# gleis-a-1.net
KiCad netlist of a schematic drawn in EAGLE
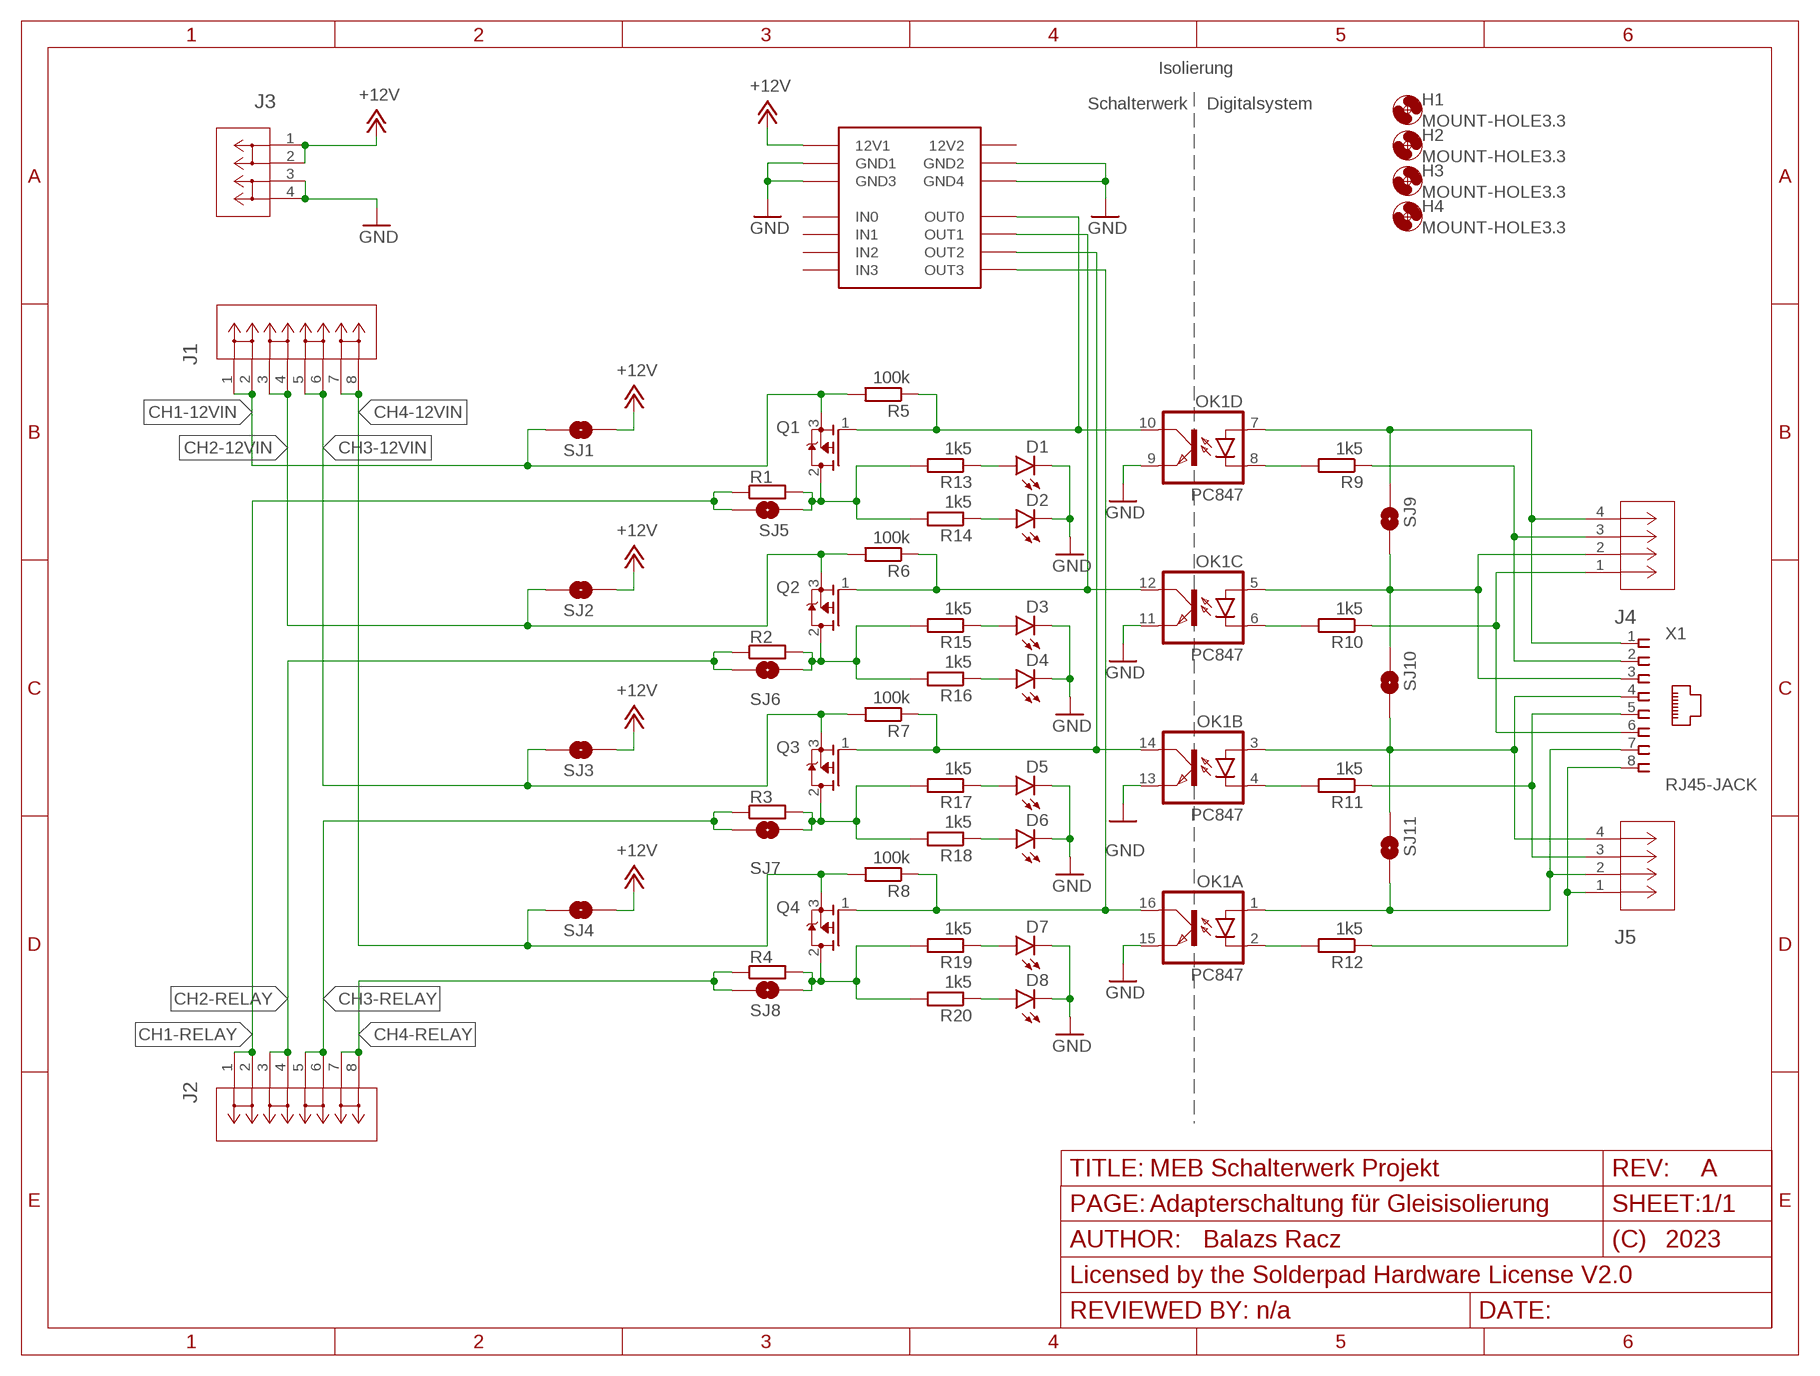
[diagram p0: schematic, sheet 1]

(export (version "E")
  (design (tool "Eeschema 10.0.6"))
  (components
    (comp (ref "D1")
      (value "LEDCHIPLED_0603")
      (footprint "eagle-import:CHIPLED_0603")
      (libsource (lib "eagle-import") (part "LEDCHIPLED_0603"))
    )
    (comp (ref "D2")
      (value "LEDHEADER")
      (footprint "eagle-import:LEDHEADER")
      (libsource (lib "eagle-import") (part "LEDHEADER"))
    )
    (comp (ref "D3")
      (value "LEDCHIPLED_0603")
      (footprint "eagle-import:CHIPLED_0603")
      (libsource (lib "eagle-import") (part "LEDCHIPLED_0603"))
    )
    (comp (ref "D4")
      (value "LEDHEADER")
      (footprint "eagle-import:LEDHEADER")
      (libsource (lib "eagle-import") (part "LEDHEADER"))
    )
    (comp (ref "D5")
      (value "LEDCHIPLED_0603")
      (footprint "eagle-import:CHIPLED_0603")
      (libsource (lib "eagle-import") (part "LEDCHIPLED_0603"))
    )
    (comp (ref "D6")
      (value "LEDHEADER")
      (footprint "eagle-import:LEDHEADER")
      (libsource (lib "eagle-import") (part "LEDHEADER"))
    )
    (comp (ref "D7")
      (value "LEDCHIPLED_0603")
      (footprint "eagle-import:CHIPLED_0603")
      (libsource (lib "eagle-import") (part "LEDCHIPLED_0603"))
    )
    (comp (ref "D8")
      (value "LEDHEADER")
      (footprint "eagle-import:LEDHEADER")
      (libsource (lib "eagle-import") (part "LEDHEADER"))
    )
    (comp (ref "H1")
      (value "MOUNT-HOLE3.3")
      (footprint "eagle-import:3,3")
      (libsource (lib "eagle-import") (part "MOUNT-HOLE3.3"))
    )
    (comp (ref "H2")
      (value "MOUNT-HOLE3.3")
      (footprint "eagle-import:3,3")
      (libsource (lib "eagle-import") (part "MOUNT-HOLE3.3"))
    )
    (comp (ref "H3")
      (value "MOUNT-HOLE3.3")
      (footprint "eagle-import:3,3")
      (libsource (lib "eagle-import") (part "MOUNT-HOLE3.3"))
    )
    (comp (ref "H4")
      (value "MOUNT-HOLE3.3")
      (footprint "eagle-import:3,3")
      (libsource (lib "eagle-import") (part "MOUNT-HOLE3.3"))
    )
    (comp (ref "J1")
      (value "PHNX_4P_508CONN_1017493")
      (footprint "eagle-import:PHNX_4P_508")
      (fields
        (field (name "MANUFACTURER_PART_NUMBER") "1017505")
        (field (name "COPYRIGHT") "Copyright (C) 2023 Ultra Librarian. All rights reserved.")
      )
      (libsource (lib "eagle-import") (part "PHNX_4P_508CONN_1017493"))
    )
    (comp (ref "J2")
      (value "PHNX_4P_508CONN_1017493")
      (footprint "eagle-import:PHNX_4P_508")
      (fields
        (field (name "MANUFACTURER_PART_NUMBER") "1017505")
        (field (name "COPYRIGHT") "Copyright (C) 2023 Ultra Librarian. All rights reserved.")
      )
      (libsource (lib "eagle-import") (part "PHNX_4P_508CONN_1017493"))
    )
    (comp (ref "J3")
      (value "PHNX_2P_508CONN_1017491")
      (footprint "eagle-import:PHNX_2P_508")
      (fields
        (field (name "MANUFACTURER_PART_NUMBER") "1017503")
        (field (name "COPYRIGHT") "Copyright (C) 2023 Ultra Librarian. All rights reserved.")
      )
      (libsource (lib "eagle-import") (part "PHNX_2P_508CONN_1017491"))
    )
    (comp (ref "J4")
      (value "PHNX_4P_350CONN_1984989_PXC")
      (footprint "eagle-import:PHNX_4P_350")
      (fields
        (field (name "MANUFACTURER_PART_NUMBER") "1984989")
        (field (name "COPYRIGHT") "Copyright (C) 2023 Ultra Librarian. All rights reserved.")
      )
      (libsource (lib "eagle-import") (part "PHNX_4P_350CONN_1984989_PXC"))
    )
    (comp (ref "J5")
      (value "PHNX_4P_350CONN_1984989_PXC")
      (footprint "eagle-import:PHNX_4P_350")
      (fields
        (field (name "MANUFACTURER_PART_NUMBER") "1984989")
        (field (name "COPYRIGHT") "Copyright (C) 2023 Ultra Librarian. All rights reserved.")
      )
      (libsource (lib "eagle-import") (part "PHNX_4P_350CONN_1984989_PXC"))
    )
    (comp (ref "OK1")
      (value "PC847")
      (footprint "eagle-import:DIL16")
      (libsource (lib "eagle-import") (part "PC847"))
    )
    (comp (ref "Q1")
      (value "P-MOSFET")
      (footprint "eagle-import:DPAK-2")
      (fields (field (name "MANUFACTURER") "Infineon"))
      (libsource (lib "eagle-import") (part "P-MOSFET"))
    )
    (comp (ref "Q2")
      (value "P-MOSFET")
      (footprint "eagle-import:DPAK-2")
      (fields (field (name "MANUFACTURER") "Infineon"))
      (libsource (lib "eagle-import") (part "P-MOSFET"))
    )
    (comp (ref "Q3")
      (value "P-MOSFET")
      (footprint "eagle-import:DPAK-2")
      (fields (field (name "MANUFACTURER") "Infineon"))
      (libsource (lib "eagle-import") (part "P-MOSFET"))
    )
    (comp (ref "Q4")
      (value "P-MOSFET")
      (footprint "eagle-import:DPAK-2")
      (fields (field (name "MANUFACTURER") "Infineon"))
      (libsource (lib "eagle-import") (part "P-MOSFET"))
    )
    (comp (ref "R1")
      (value "R-EU_VTA52")
      (footprint "eagle-import:VTA52")
      (libsource (lib "eagle-import") (part "R-EU_VTA52"))
    )
    (comp (ref "R2")
      (value "R-EU_VTA52")
      (footprint "eagle-import:VTA52")
      (libsource (lib "eagle-import") (part "R-EU_VTA52"))
    )
    (comp (ref "R3")
      (value "R-EU_VTA52")
      (footprint "eagle-import:VTA52")
      (libsource (lib "eagle-import") (part "R-EU_VTA52"))
    )
    (comp (ref "R4")
      (value "R-EU_VTA52")
      (footprint "eagle-import:VTA52")
      (libsource (lib "eagle-import") (part "R-EU_VTA52"))
    )
    (comp (ref "R5")
      (value "100k")
      (footprint "eagle-import:R0805")
      (libsource (lib "eagle-import") (part "R-EU_R0805"))
    )
    (comp (ref "R6")
      (value "100k")
      (footprint "eagle-import:R0805")
      (libsource (lib "eagle-import") (part "R-EU_R0805"))
    )
    (comp (ref "R7")
      (value "100k")
      (footprint "eagle-import:R0805")
      (libsource (lib "eagle-import") (part "R-EU_R0805"))
    )
    (comp (ref "R8")
      (value "100k")
      (footprint "eagle-import:R0805")
      (libsource (lib "eagle-import") (part "R-EU_R0805"))
    )
    (comp (ref "R9")
      (value "1k5")
      (footprint "eagle-import:R0805")
      (libsource (lib "eagle-import") (part "R-EU_R0805"))
    )
    (comp (ref "R10")
      (value "1k5")
      (footprint "eagle-import:R0805")
      (libsource (lib "eagle-import") (part "R-EU_R0805"))
    )
    (comp (ref "R11")
      (value "1k5")
      (footprint "eagle-import:R0805")
      (libsource (lib "eagle-import") (part "R-EU_R0805"))
    )
    (comp (ref "R12")
      (value "1k5")
      (footprint "eagle-import:R0805")
      (libsource (lib "eagle-import") (part "R-EU_R0805"))
    )
    (comp (ref "R13")
      (value "1k5")
      (footprint "eagle-import:R0805")
      (libsource (lib "eagle-import") (part "R-EU_R0805"))
    )
    (comp (ref "R14")
      (value "1k5")
      (footprint "eagle-import:R0805")
      (libsource (lib "eagle-import") (part "R-EU_R0805"))
    )
    (comp (ref "R15")
      (value "1k5")
      (footprint "eagle-import:R0805")
      (libsource (lib "eagle-import") (part "R-EU_R0805"))
    )
    (comp (ref "R16")
      (value "1k5")
      (footprint "eagle-import:R0805")
      (libsource (lib "eagle-import") (part "R-EU_R0805"))
    )
    (comp (ref "R17")
      (value "1k5")
      (footprint "eagle-import:R0805")
      (libsource (lib "eagle-import") (part "R-EU_R0805"))
    )
    (comp (ref "R18")
      (value "1k5")
      (footprint "eagle-import:R0805")
      (libsource (lib "eagle-import") (part "R-EU_R0805"))
    )
    (comp (ref "R19")
      (value "1k5")
      (footprint "eagle-import:R0805")
      (libsource (lib "eagle-import") (part "R-EU_R0805"))
    )
    (comp (ref "R20")
      (value "1k5")
      (footprint "eagle-import:R0805")
      (libsource (lib "eagle-import") (part "R-EU_R0805"))
    )
    (comp (ref "SJ1")
      (value "SJRND2")
      (footprint "eagle-import:SJ_RND2")
      (libsource (lib "eagle-import") (part "SJRND2"))
    )
    (comp (ref "SJ2")
      (value "SJRND2")
      (footprint "eagle-import:SJ_RND2")
      (libsource (lib "eagle-import") (part "SJRND2"))
    )
    (comp (ref "SJ3")
      (value "SJRND2")
      (footprint "eagle-import:SJ_RND2")
      (libsource (lib "eagle-import") (part "SJRND2"))
    )
    (comp (ref "SJ4")
      (value "SJRND2")
      (footprint "eagle-import:SJ_RND2")
      (libsource (lib "eagle-import") (part "SJRND2"))
    )
    (comp (ref "SJ5")
      (value "SJRND2")
      (footprint "eagle-import:SJ_RND2")
      (libsource (lib "eagle-import") (part "SJRND2"))
    )
    (comp (ref "SJ6")
      (value "SJRND2")
      (footprint "eagle-import:SJ_RND2")
      (libsource (lib "eagle-import") (part "SJRND2"))
    )
    (comp (ref "SJ7")
      (value "SJRND2")
      (footprint "eagle-import:SJ_RND2")
      (libsource (lib "eagle-import") (part "SJRND2"))
    )
    (comp (ref "SJ8")
      (value "SJRND2")
      (footprint "eagle-import:SJ_RND2")
      (libsource (lib "eagle-import") (part "SJRND2"))
    )
    (comp (ref "SJ9")
      (value "SJRND2")
      (footprint "eagle-import:SJ_RND2")
      (libsource (lib "eagle-import") (part "SJRND2"))
    )
    (comp (ref "SJ10")
      (value "SJRND2")
      (footprint "eagle-import:SJ_RND2")
      (libsource (lib "eagle-import") (part "SJRND2"))
    )
    (comp (ref "SJ11")
      (value "SJRND2")
      (footprint "eagle-import:SJ_RND2")
      (libsource (lib "eagle-import") (part "SJRND2"))
    )
    (comp (ref "X1")
      (value "RJ45-JACK")
      (footprint "eagle-import:RJ45-PULSE-E5J88")
      (libsource (lib "eagle-import") (part "RJ45-JACKRJ45-PULSE-E5J00"))
    )
    (comp (ref "X2")
      (value "IO-HAT")
      (footprint "eagle-import:IOBOARD")
      (libsource (lib "eagle-import") (part "IO-HAT"))
    )
  )
  (nets
    (net (code "1") (name "+12V") (class "Default")
      (node (ref "J3") (pin "1") (pinfunction "1_1") (pintype "passive"))
      (node (ref "J3") (pin "2") (pinfunction "2_2") (pintype "passive"))
      (node (ref "SJ1") (pin "P$2") (pinfunction "2_P$2") (pintype "passive"))
      (node (ref "SJ2") (pin "P$2") (pinfunction "2_P$2") (pintype "passive"))
      (node (ref "SJ3") (pin "P$2") (pinfunction "2_P$2") (pintype "passive"))
      (node (ref "SJ4") (pin "P$2") (pinfunction "2_P$2") (pintype "passive"))
      (node (ref "X2") (pin "P$1") (pinfunction "12V1_P$1") (pintype "power_in"))
    )
    (net (code "2") (name "/12V2") (class "Default")
      (node (ref "X2") (pin "P$22") (pinfunction "12V2_P$22") (pintype "power_in"))
    )
    (net (code "3") (name "CH1-12VIN") (class "Default")
      (node (ref "J1") (pin "1") (pinfunction "1_1") (pintype "passive"))
      (node (ref "J1") (pin "2") (pinfunction "2_2") (pintype "passive"))
      (node (ref "Q1") (pin "3") (pinfunction "S_3") (pintype "passive"))
      (node (ref "R5") (pin "2") (pinfunction "2_2") (pintype "passive"))
      (node (ref "SJ1") (pin "P$1") (pinfunction "1_P$1") (pintype "passive"))
    )
    (net (code "4") (name "CH1-RELAY") (class "Default")
      (node (ref "J2") (pin "1") (pinfunction "1_1") (pintype "passive"))
      (node (ref "J2") (pin "2") (pinfunction "2_2") (pintype "passive"))
      (node (ref "R1") (pin "1") (pinfunction "1_1") (pintype "passive"))
      (node (ref "SJ5") (pin "P$1") (pinfunction "1_P$1") (pintype "passive"))
    )
    (net (code "5") (name "CH2-12VIN") (class "Default")
      (node (ref "J1") (pin "3") (pinfunction "3_3") (pintype "passive"))
      (node (ref "J1") (pin "4") (pinfunction "4_4") (pintype "passive"))
      (node (ref "Q2") (pin "3") (pinfunction "S_3") (pintype "passive"))
      (node (ref "R6") (pin "2") (pinfunction "2_2") (pintype "passive"))
      (node (ref "SJ2") (pin "P$1") (pinfunction "1_P$1") (pintype "passive"))
    )
    (net (code "6") (name "CH2-RELAY") (class "Default")
      (node (ref "J2") (pin "3") (pinfunction "3_3") (pintype "passive"))
      (node (ref "J2") (pin "4") (pinfunction "4_4") (pintype "passive"))
      (node (ref "R2") (pin "1") (pinfunction "1_1") (pintype "passive"))
      (node (ref "SJ6") (pin "P$1") (pinfunction "1_P$1") (pintype "passive"))
    )
    (net (code "7") (name "CH3-12VIN") (class "Default")
      (node (ref "J1") (pin "5") (pinfunction "5_5") (pintype "passive"))
      (node (ref "J1") (pin "6") (pinfunction "6_6") (pintype "passive"))
      (node (ref "Q3") (pin "3") (pinfunction "S_3") (pintype "passive"))
      (node (ref "R7") (pin "2") (pinfunction "2_2") (pintype "passive"))
      (node (ref "SJ3") (pin "P$1") (pinfunction "1_P$1") (pintype "passive"))
    )
    (net (code "8") (name "CH3-RELAY") (class "Default")
      (node (ref "J2") (pin "5") (pinfunction "5_5") (pintype "passive"))
      (node (ref "J2") (pin "6") (pinfunction "6_6") (pintype "passive"))
      (node (ref "R3") (pin "1") (pinfunction "1_1") (pintype "passive"))
      (node (ref "SJ7") (pin "P$1") (pinfunction "1_P$1") (pintype "passive"))
    )
    (net (code "9") (name "CH4-12VIN") (class "Default")
      (node (ref "J1") (pin "7") (pinfunction "7_7") (pintype "passive"))
      (node (ref "J1") (pin "8") (pinfunction "8_8") (pintype "passive"))
      (node (ref "Q4") (pin "3") (pinfunction "S_3") (pintype "passive"))
      (node (ref "R8") (pin "2") (pinfunction "2_2") (pintype "passive"))
      (node (ref "SJ4") (pin "P$1") (pinfunction "1_P$1") (pintype "passive"))
    )
    (net (code "10") (name "CH4-RELAY") (class "Default")
      (node (ref "J2") (pin "7") (pinfunction "7_7") (pintype "passive"))
      (node (ref "J2") (pin "8") (pinfunction "8_8") (pintype "passive"))
      (node (ref "R4") (pin "1") (pinfunction "1_1") (pintype "passive"))
      (node (ref "SJ8") (pin "P$1") (pinfunction "1_P$1") (pintype "passive"))
    )
    (net (code "11") (name "GND") (class "Default")
      (node (ref "D1") (pin "C") (pinfunction "C_C") (pintype "passive"))
      (node (ref "D2") (pin "C") (pinfunction "C_C") (pintype "passive"))
      (node (ref "D3") (pin "C") (pinfunction "C_C") (pintype "passive"))
      (node (ref "D4") (pin "C") (pinfunction "C_C") (pintype "passive"))
      (node (ref "D5") (pin "C") (pinfunction "C_C") (pintype "passive"))
      (node (ref "D6") (pin "C") (pinfunction "C_C") (pintype "passive"))
      (node (ref "D7") (pin "C") (pinfunction "C_C") (pintype "passive"))
      (node (ref "D8") (pin "C") (pinfunction "C_C") (pintype "passive"))
      (node (ref "J3") (pin "3") (pinfunction "3_3") (pintype "passive"))
      (node (ref "J3") (pin "4") (pinfunction "4_4") (pintype "passive"))
      (node (ref "OK1") (pin "11") (pinfunction "EMIT_11") (pintype "passive"))
      (node (ref "OK1") (pin "13") (pinfunction "EMIT_13") (pintype "passive"))
      (node (ref "OK1") (pin "15") (pinfunction "EMIT_15") (pintype "passive"))
      (node (ref "OK1") (pin "9") (pinfunction "EMIT_9") (pintype "passive"))
      (node (ref "X2") (pin "P$11") (pinfunction "GND3_P$11") (pintype "power_in"))
      (node (ref "X2") (pin "P$12") (pinfunction "GND4_P$12") (pintype "power_in"))
      (node (ref "X2") (pin "P$2") (pinfunction "GND1_P$2") (pintype "power_in"))
      (node (ref "X2") (pin "P$21") (pinfunction "GND2_P$21") (pintype "power_in"))
    )
    (net (code "12") (name "Net-(D1-PadA)") (class "Default")
      (node (ref "D1") (pin "A") (pinfunction "A_A") (pintype "passive"))
      (node (ref "R13") (pin "1") (pinfunction "1_1") (pintype "passive"))
    )
    (net (code "13") (name "Net-(D2-PadA)") (class "Default")
      (node (ref "D2") (pin "A") (pinfunction "A_A") (pintype "passive"))
      (node (ref "R14") (pin "1") (pinfunction "1_1") (pintype "passive"))
    )
    (net (code "14") (name "Net-(D3-PadA)") (class "Default")
      (node (ref "D3") (pin "A") (pinfunction "A_A") (pintype "passive"))
      (node (ref "R15") (pin "1") (pinfunction "1_1") (pintype "passive"))
    )
    (net (code "15") (name "Net-(D4-PadA)") (class "Default")
      (node (ref "D4") (pin "A") (pinfunction "A_A") (pintype "passive"))
      (node (ref "R16") (pin "1") (pinfunction "1_1") (pintype "passive"))
    )
    (net (code "16") (name "Net-(D5-PadA)") (class "Default")
      (node (ref "D5") (pin "A") (pinfunction "A_A") (pintype "passive"))
      (node (ref "R17") (pin "1") (pinfunction "1_1") (pintype "passive"))
    )
    (net (code "17") (name "Net-(D6-PadA)") (class "Default")
      (node (ref "D6") (pin "A") (pinfunction "A_A") (pintype "passive"))
      (node (ref "R18") (pin "1") (pinfunction "1_1") (pintype "passive"))
    )
    (net (code "18") (name "Net-(D7-PadA)") (class "Default")
      (node (ref "D7") (pin "A") (pinfunction "A_A") (pintype "passive"))
      (node (ref "R19") (pin "1") (pinfunction "1_1") (pintype "passive"))
    )
    (net (code "19") (name "Net-(D8-PadA)") (class "Default")
      (node (ref "D8") (pin "A") (pinfunction "A_A") (pintype "passive"))
      (node (ref "R20") (pin "1") (pinfunction "1_1") (pintype "passive"))
    )
    (net (code "20") (name "Net-(J4-Pad1)") (class "Default")
      (node (ref "J4") (pin "1") (pinfunction "1_1") (pintype "passive"))
      (node (ref "R10") (pin "1") (pinfunction "1_1") (pintype "passive"))
      (node (ref "X1") (pin "6") (pinfunction "6_6") (pintype "passive"))
    )
    (net (code "21") (name "Net-(J4-Pad3)") (class "Default")
      (node (ref "J4") (pin "3") (pinfunction "3_3") (pintype "passive"))
      (node (ref "R9") (pin "1") (pinfunction "1_1") (pintype "passive"))
      (node (ref "X1") (pin "2") (pinfunction "2_2") (pintype "passive"))
    )
    (net (code "22") (name "Net-(J5-Pad1)") (class "Default")
      (node (ref "J5") (pin "1") (pinfunction "1_1") (pintype "passive"))
      (node (ref "R12") (pin "1") (pinfunction "1_1") (pintype "passive"))
      (node (ref "X1") (pin "8") (pinfunction "8_8") (pintype "passive"))
    )
    (net (code "23") (name "Net-(J5-Pad3)") (class "Default")
      (node (ref "J5") (pin "3") (pinfunction "3_3") (pintype "passive"))
      (node (ref "R11") (pin "1") (pinfunction "1_1") (pintype "passive"))
      (node (ref "X1") (pin "5") (pinfunction "5_5") (pintype "passive"))
    )
    (net (code "24") (name "Net-(OK1A-A)") (class "Default")
      (node (ref "J5") (pin "2") (pinfunction "2_2") (pintype "passive"))
      (node (ref "OK1") (pin "1") (pinfunction "A_1") (pintype "passive"))
      (node (ref "SJ11") (pin "P$1") (pinfunction "1_P$1") (pintype "passive"))
      (node (ref "X1") (pin "7") (pinfunction "7_7") (pintype "passive"))
    )
    (net (code "25") (name "Net-(OK1A-C)") (class "Default")
      (node (ref "OK1") (pin "2") (pinfunction "C_2") (pintype "passive"))
      (node (ref "R12") (pin "2") (pinfunction "2_2") (pintype "passive"))
    )
    (net (code "26") (name "Net-(OK1A-COL)") (class "Default")
      (node (ref "OK1") (pin "16") (pinfunction "COL_16") (pintype "passive"))
      (node (ref "Q4") (pin "1") (pinfunction "G_1") (pintype "passive"))
      (node (ref "R8") (pin "1") (pinfunction "1_1") (pintype "passive"))
      (node (ref "X2") (pin "P$17") (pinfunction "OUT3_P$17") (pintype "open_collector"))
    )
    (net (code "27") (name "Net-(OK1B-A)") (class "Default")
      (node (ref "J5") (pin "4") (pinfunction "4_4") (pintype "passive"))
      (node (ref "OK1") (pin "3") (pinfunction "A_3") (pintype "passive"))
      (node (ref "SJ10") (pin "P$1") (pinfunction "1_P$1") (pintype "passive"))
      (node (ref "SJ11") (pin "P$2") (pinfunction "2_P$2") (pintype "passive"))
      (node (ref "X1") (pin "4") (pinfunction "4_4") (pintype "passive"))
    )
    (net (code "28") (name "Net-(OK1B-C)") (class "Default")
      (node (ref "OK1") (pin "4") (pinfunction "C_4") (pintype "passive"))
      (node (ref "R11") (pin "2") (pinfunction "2_2") (pintype "passive"))
    )
    (net (code "29") (name "Net-(OK1B-COL)") (class "Default")
      (node (ref "OK1") (pin "14") (pinfunction "COL_14") (pintype "passive"))
      (node (ref "Q3") (pin "1") (pinfunction "G_1") (pintype "passive"))
      (node (ref "R7") (pin "1") (pinfunction "1_1") (pintype "passive"))
      (node (ref "X2") (pin "P$18") (pinfunction "OUT2_P$18") (pintype "open_collector"))
    )
    (net (code "30") (name "Net-(OK1C-A)") (class "Default")
      (node (ref "J4") (pin "2") (pinfunction "2_2") (pintype "passive"))
      (node (ref "OK1") (pin "5") (pinfunction "A_5") (pintype "passive"))
      (node (ref "SJ10") (pin "P$2") (pinfunction "2_P$2") (pintype "passive"))
      (node (ref "SJ9") (pin "P$1") (pinfunction "1_P$1") (pintype "passive"))
      (node (ref "X1") (pin "3") (pinfunction "3_3") (pintype "passive"))
    )
    (net (code "31") (name "Net-(OK1C-C)") (class "Default")
      (node (ref "OK1") (pin "6") (pinfunction "C_6") (pintype "passive"))
      (node (ref "R10") (pin "2") (pinfunction "2_2") (pintype "passive"))
    )
    (net (code "32") (name "Net-(OK1C-COL)") (class "Default")
      (node (ref "OK1") (pin "12") (pinfunction "COL_12") (pintype "passive"))
      (node (ref "Q2") (pin "1") (pinfunction "G_1") (pintype "passive"))
      (node (ref "R6") (pin "1") (pinfunction "1_1") (pintype "passive"))
      (node (ref "X2") (pin "P$19") (pinfunction "OUT1_P$19") (pintype "open_collector"))
    )
    (net (code "33") (name "Net-(OK1D-A)") (class "Default")
      (node (ref "J4") (pin "4") (pinfunction "4_4") (pintype "passive"))
      (node (ref "OK1") (pin "7") (pinfunction "A_7") (pintype "passive"))
      (node (ref "SJ9") (pin "P$2") (pinfunction "2_P$2") (pintype "passive"))
      (node (ref "X1") (pin "1") (pinfunction "1_1") (pintype "passive"))
    )
    (net (code "34") (name "Net-(OK1D-C)") (class "Default")
      (node (ref "OK1") (pin "8") (pinfunction "C_8") (pintype "passive"))
      (node (ref "R9") (pin "2") (pinfunction "2_2") (pintype "passive"))
    )
    (net (code "35") (name "Net-(OK1D-COL)") (class "Default")
      (node (ref "OK1") (pin "10") (pinfunction "COL_10") (pintype "passive"))
      (node (ref "Q1") (pin "1") (pinfunction "G_1") (pintype "passive"))
      (node (ref "R5") (pin "1") (pinfunction "1_1") (pintype "passive"))
      (node (ref "X2") (pin "P$20") (pinfunction "OUT0_P$20") (pintype "open_collector"))
    )
    (net (code "36") (name "Net-(Q1-D)") (class "Default")
      (node (ref "Q1") (pin "2") (pinfunction "D_2") (pintype "passive"))
      (node (ref "R1") (pin "2") (pinfunction "2_2") (pintype "passive"))
      (node (ref "R13") (pin "2") (pinfunction "2_2") (pintype "passive"))
      (node (ref "R14") (pin "2") (pinfunction "2_2") (pintype "passive"))
      (node (ref "SJ5") (pin "P$2") (pinfunction "2_P$2") (pintype "passive"))
    )
    (net (code "37") (name "Net-(Q2-D)") (class "Default")
      (node (ref "Q2") (pin "2") (pinfunction "D_2") (pintype "passive"))
      (node (ref "R15") (pin "2") (pinfunction "2_2") (pintype "passive"))
      (node (ref "R16") (pin "2") (pinfunction "2_2") (pintype "passive"))
      (node (ref "R2") (pin "2") (pinfunction "2_2") (pintype "passive"))
      (node (ref "SJ6") (pin "P$2") (pinfunction "2_P$2") (pintype "passive"))
    )
    (net (code "38") (name "Net-(Q3-D)") (class "Default")
      (node (ref "Q3") (pin "2") (pinfunction "D_2") (pintype "passive"))
      (node (ref "R17") (pin "2") (pinfunction "2_2") (pintype "passive"))
      (node (ref "R18") (pin "2") (pinfunction "2_2") (pintype "passive"))
      (node (ref "R3") (pin "2") (pinfunction "2_2") (pintype "passive"))
      (node (ref "SJ7") (pin "P$2") (pinfunction "2_P$2") (pintype "passive"))
    )
    (net (code "39") (name "Net-(Q4-D)") (class "Default")
      (node (ref "Q4") (pin "2") (pinfunction "D_2") (pintype "passive"))
      (node (ref "R19") (pin "2") (pinfunction "2_2") (pintype "passive"))
      (node (ref "R20") (pin "2") (pinfunction "2_2") (pintype "passive"))
      (node (ref "R4") (pin "2") (pinfunction "2_2") (pintype "passive"))
      (node (ref "SJ8") (pin "P$2") (pinfunction "2_P$2") (pintype "passive"))
    )
    (net (code "40") (name "unconnected-(X2A-IN0-PadP$3)") (class "Default")
      (node (ref "X2") (pin "P$3") (pinfunction "IN0_P$3") (pintype "input"))
    )
    (net (code "41") (name "unconnected-(X2A-IN1-PadP$4)") (class "Default")
      (node (ref "X2") (pin "P$4") (pinfunction "IN1_P$4") (pintype "input"))
    )
    (net (code "42") (name "unconnected-(X2A-IN2-PadP$5)") (class "Default")
      (node (ref "X2") (pin "P$5") (pinfunction "IN2_P$5") (pintype "input"))
    )
    (net (code "43") (name "unconnected-(X2A-IN3-PadP$6)") (class "Default")
      (node (ref "X2") (pin "P$6") (pinfunction "IN3_P$6") (pintype "input"))
    )
  )
)
